# DM1092_QWIIC.net
KiCad netlist of a schematic drawn in Altium Designer
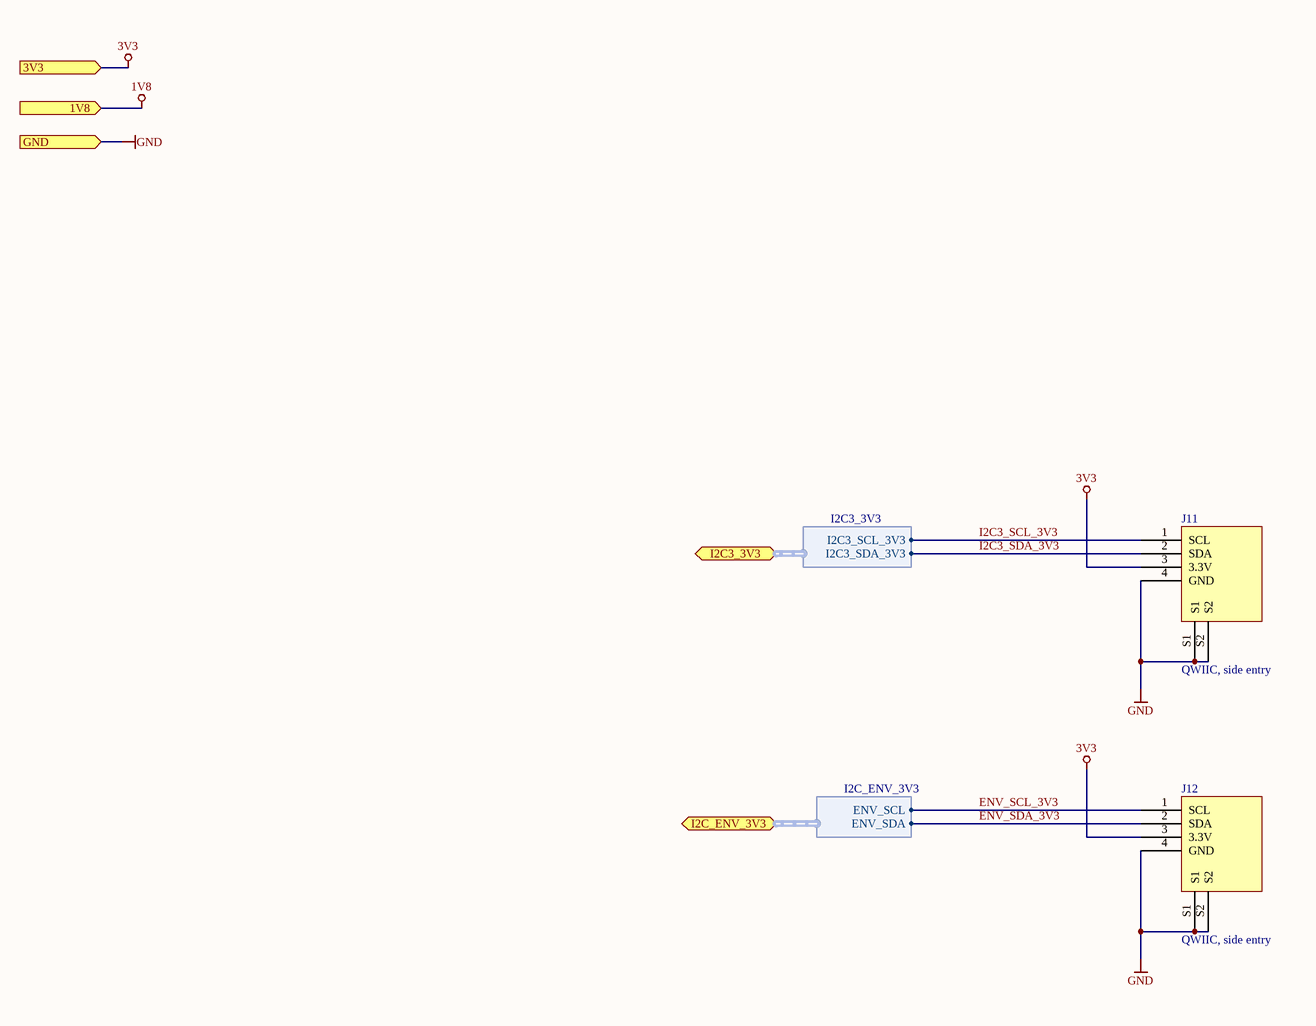
[diagram p0: DM1092_QWIIC.SchDoc]

(export (version "E")
  (design (tool "Eeschema 10.0.6"))
  (components
    (comp (ref "J11")
      (value "QWIIC, side entry")
      (footprint "SM04B-SRSS-TB(LF)(SN)")
      (description "Connector Header, Side Entry, SR Series, 4 Position, 1.00mm, 50V, Surface Mount, Tin, Natural")
      (libsource (lib "DM1092_R0M0E0") (part "SM04B-SRSS-TB(LF)(SN)"))
    )
    (comp (ref "J12")
      (value "QWIIC, side entry")
      (footprint "SM04B-SRSS-TB(LF)(SN)")
      (description "Connector Header, Side Entry, SR Series, 4 Position, 1.00mm, 50V, Surface Mount, Tin, Natural")
      (libsource (lib "DM1092_R0M0E0") (part "SM04B-SRSS-TB(LF)(SN)"))
    )
  )
  (nets
    (net (code "3") (name "/ENV_SCL_3V3") (class "Default")
      (node (ref "J12") (pin "1") (pinfunction "SCL_1") (pintype "passive"))
    )
    (net (code "4") (name "/ENV_SDA_3V3") (class "Default")
      (node (ref "J12") (pin "2") (pinfunction "SDA_2") (pintype "passive"))
    )
    (net (code "5") (name "/I2C3_SCL_3V3") (class "Default")
      (node (ref "J11") (pin "1") (pinfunction "SCL_1") (pintype "passive"))
    )
    (net (code "6") (name "/I2C3_SDA_3V3") (class "Default")
      (node (ref "J11") (pin "2") (pinfunction "SDA_2") (pintype "passive"))
    )
    (net (code "10") (name "3V3") (class "Default")
      (node (ref "J11") (pin "3") (pinfunction "3.3V_3") (pintype "passive"))
      (node (ref "J12") (pin "3") (pinfunction "3.3V_3") (pintype "passive"))
    )
    (net (code "11") (name "GND") (class "Default")
      (node (ref "J11") (pin "4") (pinfunction "GND_4") (pintype "passive"))
      (node (ref "J11") (pin "S1") (pinfunction "S1_S1") (pintype "passive"))
      (node (ref "J11") (pin "S2") (pinfunction "S2_S2") (pintype "passive"))
      (node (ref "J12") (pin "4") (pinfunction "GND_4") (pintype "passive"))
      (node (ref "J12") (pin "S1") (pinfunction "S1_S1") (pintype "passive"))
      (node (ref "J12") (pin "S2") (pinfunction "S2_S2") (pintype "passive"))
    )
  )
)
